# Philophrosyne.net
KiCad netlist of a schematic drawn in EAGLE
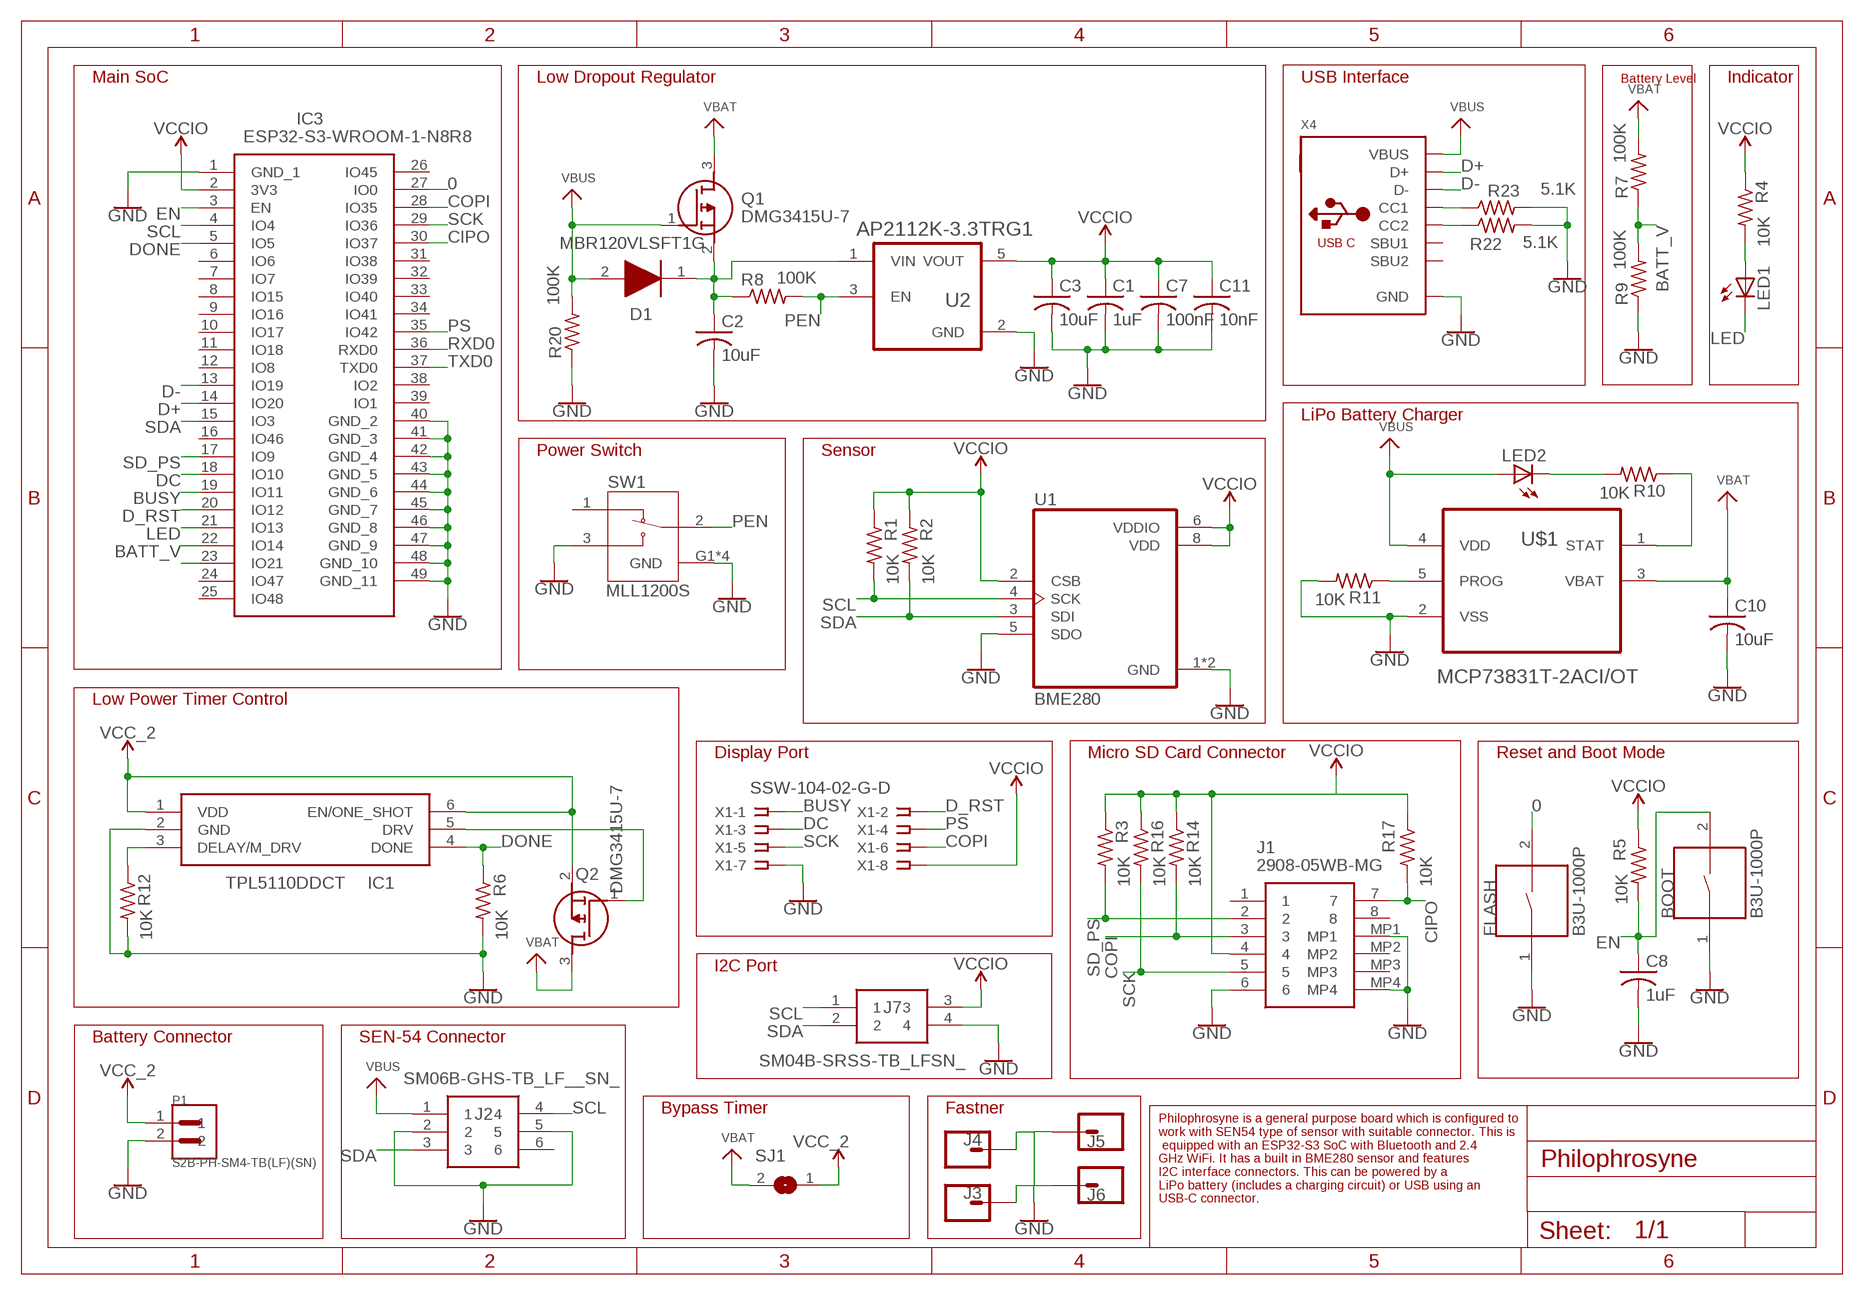
[diagram p0: schematic, sheet 1]

(export (version "E")
  (design (tool "Eeschema 10.0.6"))
  (components
    (comp (ref "BOOT")
      (value "B3U-1000P")
      (footprint "eagle-import:SW_B3U-1000P")
      (fields (field (name "MF") "Omron"))
      (libsource (lib "eagle-import") (part "B3U-1000P"))
    )
    (comp (ref "C1")
      (value "1uF")
      (footprint "eagle-import:C0402")
      (libsource (lib "eagle-import") (part "C-USC0402"))
    )
    (comp (ref "C2")
      (value "10uF")
      (footprint "eagle-import:C0402")
      (libsource (lib "eagle-import") (part "C-USC0402"))
    )
    (comp (ref "C3")
      (value "10uF")
      (footprint "eagle-import:C0402")
      (libsource (lib "eagle-import") (part "C-USC0402"))
    )
    (comp (ref "C7")
      (value "100nF")
      (footprint "eagle-import:C0402")
      (libsource (lib "eagle-import") (part "C-USC0402"))
    )
    (comp (ref "C8")
      (value "1uF")
      (footprint "eagle-import:C0402")
      (libsource (lib "eagle-import") (part "C-USC0402"))
    )
    (comp (ref "C10")
      (value "10uF")
      (footprint "eagle-import:C0402")
      (libsource (lib "eagle-import") (part "C-USC0402"))
    )
    (comp (ref "C11")
      (value "10nF")
      (footprint "eagle-import:C0402")
      (libsource (lib "eagle-import") (part "C-USC0402"))
    )
    (comp (ref "D1")
      (value "MBR120VLSFT1G")
      (footprint "eagle-import:SODFL3616X98N")
      (fields (field (name "MOUSER_PART_NUMBER") "863-MBR120VLSFT1G"))
      (libsource (lib "eagle-import") (part "MBR120VLSFT1G"))
    )
    (comp (ref "FLASH")
      (value "B3U-1000P")
      (footprint "eagle-import:SW_B3U-1000P")
      (fields (field (name "MF") "Omron"))
      (libsource (lib "eagle-import") (part "B3U-1000P"))
    )
    (comp (ref "IC1")
      (value "TPL5110DDCT")
      (footprint "eagle-import:SOT95P280X110-6N")
      (fields (field (name "MOUSER_PART_NUMBER") "595-TPL5110DDCT"))
      (libsource (lib "eagle-import") (part "TPL5110DDCT"))
    )
    (comp (ref "IC3")
      (value "ESP32-S3-WROOM-1-N8R8")
      (footprint "eagle-import:ESP32S3WROOM1N8R8")
      (fields (field (name "MOUSER_PART_NUMBER") "356-EP32S3WROOM1N8R8"))
      (libsource (lib "eagle-import") (part "ESP32-S3-WROOM-1-N8R8"))
    )
    (comp (ref "J1")
      (value "2908-05WB-MG")
      (footprint "eagle-import:290805WBMG")
      (fields (field (name "MOUSER_PART_NUMBER") "517-2908-05WB-MG"))
      (libsource (lib "eagle-import") (part "2908-05WB-MG"))
    )
    (comp (ref "J2")
      (value "SM06B-GHS-TB_LF__SN_")
      (footprint "eagle-import:SM06B-GHS-TB")
      (fields (field (name "ARROW_PART_NUMBER") "SM06B-GHS-TB(LF)(SN)"))
      (libsource (lib "eagle-import") (part "SM06B-GHS-TB_LF__SN_"))
    )
    (comp (ref "J3")
      (value "CONN_01PTH_2MM")
      (footprint "eagle-import:1X01_2MM")
      (libsource (lib "eagle-import") (part "CONN_01PTH_2MM"))
    )
    (comp (ref "J4")
      (value "CONN_01PTH_2MM")
      (footprint "eagle-import:1X01_2MM")
      (libsource (lib "eagle-import") (part "CONN_01PTH_2MM"))
    )
    (comp (ref "J5")
      (value "CONN_01PTH_2MM")
      (footprint "eagle-import:1X01_2MM")
      (libsource (lib "eagle-import") (part "CONN_01PTH_2MM"))
    )
    (comp (ref "J6")
      (value "CONN_01PTH_2MM")
      (footprint "eagle-import:1X01_2MM")
      (libsource (lib "eagle-import") (part "CONN_01PTH_2MM"))
    )
    (comp (ref "J7")
      (value "SM04B-SRSS-TB_LFSN_")
      (footprint "eagle-import:SM04B-SRSS-TB(LFSN)")
      (fields (field (name "MANUFACTURER_PART_NUMBER") "SM04B-SRSS-TB(LFSN)"))
      (libsource (lib "eagle-import") (part "SM04B-SRSS-TB_LFSN_"))
    )
    (comp (ref "LED1")
      (value "LEDCHIP-LED0603")
      (footprint "eagle-import:CHIP-LED0603")
      (libsource (lib "eagle-import") (part "LEDCHIP-LED0603"))
    )
    (comp (ref "LED2")
      (value "LEDCHIP-LED0603")
      (footprint "eagle-import:CHIP-LED0603")
      (libsource (lib "eagle-import") (part "LEDCHIP-LED0603"))
    )
    (comp (ref "P1")
      (value "S2B-PH-SM4-TB(LF)(SN)")
      (footprint "eagle-import:JST_S2B-PH-SM4-TB(LF)(SN)")
      (fields (field (name "MF") "JST Sales") (field (name "MP") "S2B-PH-SM4-TB _LF__SN_"))
      (libsource (lib "eagle-import") (part "S2B-PH-SM4-TB(LF)(SN)"))
    )
    (comp (ref "Q1")
      (value "DMG3415U-7")
      (footprint "eagle-import:SOT96P240X100-3N")
      (fields (field (name "LCSC_PART_NUMBER") "C96616"))
      (libsource (lib "eagle-import") (part "DMG3415U-7"))
    )
    (comp (ref "Q2")
      (value "DMG3415U-7")
      (footprint "eagle-import:SOT96P240X100-3N")
      (fields (field (name "LCSC_PART_NUMBER") "C96616"))
      (libsource (lib "eagle-import") (part "DMG3415U-7"))
    )
    (comp (ref "R1")
      (value "10K")
      (footprint "eagle-import:R0402")
      (libsource (lib "eagle-import") (part "R-US_R0402"))
    )
    (comp (ref "R2")
      (value "10K")
      (footprint "eagle-import:R0402")
      (libsource (lib "eagle-import") (part "R-US_R0402"))
    )
    (comp (ref "R3")
      (value "10K")
      (footprint "eagle-import:R0402")
      (libsource (lib "eagle-import") (part "R-US_R0402"))
    )
    (comp (ref "R4")
      (value "10K")
      (footprint "eagle-import:R0402")
      (libsource (lib "eagle-import") (part "R-US_R0402"))
    )
    (comp (ref "R5")
      (value "10K")
      (footprint "eagle-import:R0402")
      (libsource (lib "eagle-import") (part "R-US_R0402"))
    )
    (comp (ref "R6")
      (value "10K")
      (footprint "eagle-import:R0402")
      (libsource (lib "eagle-import") (part "R-US_R0402"))
    )
    (comp (ref "R7")
      (value "100K")
      (footprint "eagle-import:R0402")
      (libsource (lib "eagle-import") (part "R-US_R0402"))
    )
    (comp (ref "R8")
      (value "100K")
      (footprint "eagle-import:R0402")
      (libsource (lib "eagle-import") (part "R-US_R0402"))
    )
    (comp (ref "R9")
      (value "100K")
      (footprint "eagle-import:R0402")
      (libsource (lib "eagle-import") (part "R-US_R0402"))
    )
    (comp (ref "R10")
      (value "10K")
      (footprint "eagle-import:R0402")
      (libsource (lib "eagle-import") (part "R-US_R0402"))
    )
    (comp (ref "R11")
      (value "10K")
      (footprint "eagle-import:R0402")
      (libsource (lib "eagle-import") (part "R-US_R0402"))
    )
    (comp (ref "R12")
      (value "10K")
      (footprint "eagle-import:R0402")
      (libsource (lib "eagle-import") (part "R-US_R0402"))
    )
    (comp (ref "R14")
      (value "10K")
      (footprint "eagle-import:R0402")
      (libsource (lib "eagle-import") (part "R-US_R0402"))
    )
    (comp (ref "R16")
      (value "10K")
      (footprint "eagle-import:R0402")
      (libsource (lib "eagle-import") (part "R-US_R0402"))
    )
    (comp (ref "R17")
      (value "10K")
      (footprint "eagle-import:R0402")
      (libsource (lib "eagle-import") (part "R-US_R0402"))
    )
    (comp (ref "R20")
      (value "100K")
      (footprint "eagle-import:R0402")
      (libsource (lib "eagle-import") (part "R-US_R0402"))
    )
    (comp (ref "R22")
      (value "5.1K")
      (footprint "eagle-import:R0402")
      (libsource (lib "eagle-import") (part "R-US_R0402"))
    )
    (comp (ref "R23")
      (value "5.1K")
      (footprint "eagle-import:R0402")
      (libsource (lib "eagle-import") (part "R-US_R0402"))
    )
    (comp (ref "SJ1") (value "SJ") (footprint "eagle-import:SJ") (libsource (lib "eagle-import") (part "SJ")))
    (comp (ref "SW1")
      (value "MLL1200S")
      (footprint "eagle-import:SW_MLL1200S")
      (fields (field (name "COMMENT") "1437575-1") (field (name "MF") "TE Connectivity"))
      (libsource (lib "eagle-import") (part "MLL1200S"))
    )
    (comp (ref "U$1")
      (value "MCP73831T-2ACI/OT")
      (footprint "eagle-import:SOT95P280X145-5N")
      (fields (field (name "MF") "Microchip"))
      (libsource (lib "eagle-import") (part "MCP73831T-2ACI/OT"))
    )
    (comp (ref "U1")
      (value "BME280")
      (footprint "eagle-import:PSON65P250X250X100-8N")
      (fields (field (name "MF") "Bosch"))
      (libsource (lib "eagle-import") (part "BME280"))
    )
    (comp (ref "U2")
      (value "AP2112K-3.3TRG1")
      (footprint "eagle-import:SOT95P285X140-5N")
      (fields (field (name "MF") "Diodes Inc."))
      (libsource (lib "eagle-import") (part "AP2112K-3.3TRG1"))
    )
    (comp (ref "X1")
      (value "SSW-104-02-G-D")
      (footprint "eagle-import:SSW-104-02-G-D")
      (fields (field (name "MF") "Samtec Inc."))
      (libsource (lib "eagle-import") (part "SSW-104-02-G-D"))
    )
    (comp (ref "X4")
      (value "MICROBUILDER_USB_C")
      (footprint "eagle-import:MICROBUILDER_USB_C_CUSB31-CFM2AX-01-X")
      (libsource (lib "eagle-import") (part "MICROBUILDER_USB_C"))
    )
  )
  (nets
    (net (code "1") (name "/0") (class "Default")
      (node (ref "FLASH") (pin "2") (pinfunction "2_2") (pintype "passive"))
      (node (ref "IC3") (pin "27") (pinfunction "IO0_27") (pintype "bidirectional"))
    )
    (net (code "2") (name "/BATT_V") (class "Default")
      (node (ref "IC3") (pin "22") (pinfunction "IO14_22") (pintype "bidirectional"))
      (node (ref "R7") (pin "1") (pinfunction "1_1") (pintype "passive"))
      (node (ref "R9") (pin "2") (pinfunction "2_2") (pintype "passive"))
    )
    (net (code "3") (name "/BUSY") (class "Default")
      (node (ref "IC3") (pin "19") (pinfunction "IO11_19") (pintype "bidirectional"))
      (node (ref "X1") (pin "1") (pinfunction "1_1") (pintype "passive"))
    )
    (net (code "4") (name "/CIPO") (class "Default")
      (node (ref "IC3") (pin "30") (pinfunction "IO37_30") (pintype "bidirectional"))
      (node (ref "J1") (pin "7") (pinfunction "7_7") (pintype "bidirectional"))
      (node (ref "R17") (pin "2") (pinfunction "2_2") (pintype "passive"))
    )
    (net (code "5") (name "/COPI") (class "Default")
      (node (ref "IC3") (pin "28") (pinfunction "IO35_28") (pintype "bidirectional"))
      (node (ref "J1") (pin "3") (pinfunction "3_3") (pintype "bidirectional"))
      (node (ref "R14") (pin "2") (pinfunction "2_2") (pintype "passive"))
      (node (ref "X1") (pin "6") (pinfunction "1_6") (pintype "passive"))
    )
    (net (code "6") (name "/D+") (class "Default")
      (node (ref "IC3") (pin "14") (pinfunction "IO20_14") (pintype "bidirectional"))
      (node (ref "X4") (pin "A6") (pinfunction "D+_A6") (pintype "bidirectional"))
      (node (ref "X4") (pin "B6") (pinfunction "D+_B6") (pintype "bidirectional"))
    )
    (net (code "7") (name "/D-") (class "Default")
      (node (ref "IC3") (pin "13") (pinfunction "IO19_13") (pintype "bidirectional"))
      (node (ref "X4") (pin "A7") (pinfunction "D-_A7") (pintype "bidirectional"))
      (node (ref "X4") (pin "B7") (pinfunction "D-_B7") (pintype "bidirectional"))
    )
    (net (code "8") (name "/DC") (class "Default")
      (node (ref "IC3") (pin "18") (pinfunction "IO10_18") (pintype "bidirectional"))
      (node (ref "X1") (pin "3") (pinfunction "1_3") (pintype "passive"))
    )
    (net (code "9") (name "/DONE") (class "Default")
      (node (ref "IC1") (pin "4") (pinfunction "DONE_4") (pintype "bidirectional"))
      (node (ref "IC3") (pin "5") (pinfunction "IO5_5") (pintype "bidirectional"))
      (node (ref "R6") (pin "1") (pinfunction "1_1") (pintype "passive"))
    )
    (net (code "10") (name "/D_RST") (class "Default")
      (node (ref "IC3") (pin "20") (pinfunction "IO12_20") (pintype "bidirectional"))
      (node (ref "X1") (pin "2") (pinfunction "1_2") (pintype "passive"))
    )
    (net (code "11") (name "/EN") (class "Default")
      (node (ref "BOOT") (pin "2") (pinfunction "2_2") (pintype "passive"))
      (node (ref "C8") (pin "1") (pinfunction "1_1") (pintype "passive"))
      (node (ref "IC3") (pin "3") (pinfunction "EN_3") (pintype "bidirectional"))
      (node (ref "R5") (pin "2") (pinfunction "2_2") (pintype "passive"))
    )
    (net (code "12") (name "/LED") (class "Default")
      (node (ref "IC3") (pin "21") (pinfunction "IO13_21") (pintype "bidirectional"))
      (node (ref "LED1") (pin "C") (pinfunction "C_C") (pintype "passive"))
    )
    (net (code "13") (name "/PEN") (class "Default")
      (node (ref "R8") (pin "2") (pinfunction "2_2") (pintype "passive"))
      (node (ref "SW1") (pin "2") (pinfunction "2_2") (pintype "passive"))
      (node (ref "U2") (pin "3") (pinfunction "EN_3") (pintype "input"))
    )
    (net (code "14") (name "/PS") (class "Default")
      (node (ref "IC3") (pin "35") (pinfunction "IO42_35") (pintype "bidirectional"))
      (node (ref "X1") (pin "4") (pinfunction "1_4") (pintype "passive"))
    )
    (net (code "15") (name "/RXD0") (class "Default")
      (node (ref "IC3") (pin "36") (pinfunction "RXD0_36") (pintype "bidirectional"))
    )
    (net (code "16") (name "/SCK") (class "Default")
      (node (ref "IC3") (pin "29") (pinfunction "IO36_29") (pintype "bidirectional"))
      (node (ref "J1") (pin "5") (pinfunction "5_5") (pintype "bidirectional"))
      (node (ref "R16") (pin "2") (pinfunction "2_2") (pintype "passive"))
      (node (ref "X1") (pin "5") (pinfunction "1_5") (pintype "passive"))
    )
    (net (code "17") (name "/SCL") (class "Default")
      (node (ref "IC3") (pin "4") (pinfunction "IO4_4") (pintype "bidirectional"))
      (node (ref "J2") (pin "4") (pinfunction "4_4") (pintype "bidirectional"))
      (node (ref "J7") (pin "1") (pinfunction "1_1") (pintype "bidirectional"))
      (node (ref "R1") (pin "2") (pinfunction "2_2") (pintype "passive"))
      (node (ref "U1") (pin "4") (pinfunction "SCK_4") (pintype "input"))
    )
    (net (code "18") (name "/SDA") (class "Default")
      (node (ref "IC3") (pin "15") (pinfunction "IO3_15") (pintype "bidirectional"))
      (node (ref "J2") (pin "3") (pinfunction "3_3") (pintype "bidirectional"))
      (node (ref "J7") (pin "2") (pinfunction "2_2") (pintype "bidirectional"))
      (node (ref "R2") (pin "2") (pinfunction "2_2") (pintype "passive"))
      (node (ref "U1") (pin "3") (pinfunction "SDI_3") (pintype "bidirectional"))
    )
    (net (code "19") (name "/SD_PS") (class "Default")
      (node (ref "IC3") (pin "17") (pinfunction "IO9_17") (pintype "bidirectional"))
      (node (ref "J1") (pin "2") (pinfunction "2_2") (pintype "bidirectional"))
      (node (ref "R3") (pin "2") (pinfunction "2_2") (pintype "passive"))
    )
    (net (code "20") (name "/TXD0") (class "Default")
      (node (ref "IC3") (pin "37") (pinfunction "TXD0_37") (pintype "bidirectional"))
    )
    (net (code "21") (name "GND") (class "Default")
      (node (ref "BOOT") (pin "1") (pinfunction "1_1") (pintype "passive"))
      (node (ref "C1") (pin "2") (pinfunction "2_2") (pintype "passive"))
      (node (ref "C10") (pin "2") (pinfunction "2_2") (pintype "passive"))
      (node (ref "C11") (pin "2") (pinfunction "2_2") (pintype "passive"))
      (node (ref "C2") (pin "2") (pinfunction "2_2") (pintype "passive"))
      (node (ref "C3") (pin "2") (pinfunction "2_2") (pintype "passive"))
      (node (ref "C7") (pin "2") (pinfunction "2_2") (pintype "passive"))
      (node (ref "C8") (pin "2") (pinfunction "2_2") (pintype "passive"))
      (node (ref "FLASH") (pin "1") (pinfunction "1_1") (pintype "passive"))
      (node (ref "IC1") (pin "2") (pinfunction "GND_2") (pintype "bidirectional"))
      (node (ref "IC3") (pin "1") (pinfunction "GND_1_1") (pintype "bidirectional"))
      (node (ref "IC3") (pin "40") (pinfunction "GND_2_40") (pintype "bidirectional"))
      (node (ref "IC3") (pin "41") (pinfunction "GND_3_41") (pintype "bidirectional"))
      (node (ref "IC3") (pin "42") (pinfunction "GND_4_42") (pintype "bidirectional"))
      (node (ref "IC3") (pin "43") (pinfunction "GND_5_43") (pintype "bidirectional"))
      (node (ref "IC3") (pin "44") (pinfunction "GND_6_44") (pintype "bidirectional"))
      (node (ref "IC3") (pin "45") (pinfunction "GND_7_45") (pintype "bidirectional"))
      (node (ref "IC3") (pin "46") (pinfunction "GND_8_46") (pintype "bidirectional"))
      (node (ref "IC3") (pin "47") (pinfunction "GND_9_47") (pintype "bidirectional"))
      (node (ref "IC3") (pin "48") (pinfunction "GND_10_48") (pintype "bidirectional"))
      (node (ref "IC3") (pin "49") (pinfunction "GND_11_49") (pintype "bidirectional"))
      (node (ref "J1") (pin "6") (pinfunction "6_6") (pintype "bidirectional"))
      (node (ref "J1") (pin "MP1") (pinfunction "MP1_MP1") (pintype "bidirectional"))
      (node (ref "J1") (pin "MP4") (pinfunction "MP4_MP4") (pintype "bidirectional"))
      (node (ref "J2") (pin "2") (pinfunction "2_2") (pintype "bidirectional"))
      (node (ref "J2") (pin "5") (pinfunction "5_5") (pintype "bidirectional"))
      (node (ref "J3") (pin "1") (pinfunction "1_1") (pintype "passive"))
      (node (ref "J4") (pin "1") (pinfunction "1_1") (pintype "passive"))
      (node (ref "J5") (pin "1") (pinfunction "1_1") (pintype "passive"))
      (node (ref "J6") (pin "1") (pinfunction "1_1") (pintype "passive"))
      (node (ref "J7") (pin "4") (pinfunction "4_4") (pintype "bidirectional"))
      (node (ref "P1") (pin "2") (pinfunction "2_2") (pintype "passive"))
      (node (ref "R11") (pin "2") (pinfunction "2_2") (pintype "passive"))
      (node (ref "R12") (pin "2") (pinfunction "2_2") (pintype "passive"))
      (node (ref "R20") (pin "1") (pinfunction "1_1") (pintype "passive"))
      (node (ref "R22") (pin "2") (pinfunction "2_2") (pintype "passive"))
      (node (ref "R23") (pin "2") (pinfunction "2_2") (pintype "passive"))
      (node (ref "R6") (pin "2") (pinfunction "2_2") (pintype "passive"))
      (node (ref "R9") (pin "1") (pinfunction "1_1") (pintype "passive"))
      (node (ref "SW1") (pin "3") (pinfunction "3_3") (pintype "passive"))
      (node (ref "SW1") (pin "G1") (pinfunction "GND_G1") (pintype "power_in"))
      (node (ref "SW1") (pin "G2") (pinfunction "GND_G2") (pintype "power_in"))
      (node (ref "SW1") (pin "G3") (pinfunction "GND_G3") (pintype "power_in"))
      (node (ref "SW1") (pin "G4") (pinfunction "GND_G4") (pintype "power_in"))
      (node (ref "U$1") (pin "2") (pinfunction "VSS_2") (pintype "power_in"))
      (node (ref "U1") (pin "1") (pinfunction "GND_1") (pintype "power_in"))
      (node (ref "U1") (pin "5") (pinfunction "SDO_5") (pintype "bidirectional"))
      (node (ref "U1") (pin "7") (pinfunction "GND_7") (pintype "power_in"))
      (node (ref "U2") (pin "2") (pinfunction "GND_2") (pintype "power_in"))
      (node (ref "X1") (pin "7") (pinfunction "1_7") (pintype "passive"))
      (node (ref "X4") (pin "A1B12") (pinfunction "GND_A1B12") (pintype "power_in"))
      (node (ref "X4") (pin "B1A12") (pinfunction "GND_B1A12") (pintype "power_in"))
    )
    (net (code "22") (name "Net-(D1-K)") (class "Default")
      (node (ref "C2") (pin "1") (pinfunction "1_1") (pintype "passive"))
      (node (ref "D1") (pin "1") (pinfunction "K_1") (pintype "bidirectional"))
      (node (ref "Q1") (pin "2") (pinfunction "S_2") (pintype "bidirectional"))
      (node (ref "R8") (pin "1") (pinfunction "1_1") (pintype "passive"))
      (node (ref "U2") (pin "1") (pinfunction "VIN_1") (pintype "power_in"))
    )
    (net (code "23") (name "Net-(IC1-DELAY{slash}M_DRV)") (class "Default")
      (node (ref "IC1") (pin "3") (pinfunction "DELAY/M_DRV_3") (pintype "bidirectional"))
      (node (ref "R12") (pin "1") (pinfunction "1_1") (pintype "passive"))
    )
    (net (code "24") (name "Net-(IC1-DRV)") (class "Default")
      (node (ref "IC1") (pin "5") (pinfunction "DRV_5") (pintype "bidirectional"))
      (node (ref "Q2") (pin "1") (pinfunction "G_1") (pintype "bidirectional"))
    )
    (net (code "25") (name "Net-(LED1-PadA)") (class "Default")
      (node (ref "LED1") (pin "A") (pinfunction "A_A") (pintype "passive"))
      (node (ref "R4") (pin "2") (pinfunction "2_2") (pintype "passive"))
    )
    (net (code "26") (name "Net-(LED2-PadC)") (class "Default")
      (node (ref "LED2") (pin "C") (pinfunction "C_C") (pintype "passive"))
      (node (ref "R10") (pin "2") (pinfunction "2_2") (pintype "passive"))
    )
    (net (code "27") (name "Net-(U$1-PROG)") (class "Default")
      (node (ref "R11") (pin "1") (pinfunction "1_1") (pintype "passive"))
      (node (ref "U$1") (pin "5") (pinfunction "PROG_5") (pintype "input"))
    )
    (net (code "28") (name "Net-(U$1-STAT)") (class "Default")
      (node (ref "R10") (pin "1") (pinfunction "1_1") (pintype "passive"))
      (node (ref "U$1") (pin "1") (pinfunction "STAT_1") (pintype "output"))
    )
    (net (code "29") (name "Net-(X4-CC1)") (class "Default")
      (node (ref "R23") (pin "1") (pinfunction "1_1") (pintype "passive"))
      (node (ref "X4") (pin "A5") (pinfunction "CC1_A5") (pintype "bidirectional"))
    )
    (net (code "30") (name "Net-(X4-CC2)") (class "Default")
      (node (ref "R22") (pin "1") (pinfunction "1_1") (pintype "passive"))
      (node (ref "X4") (pin "B5") (pinfunction "CC2_B5") (pintype "bidirectional"))
    )
    (net (code "31") (name "VBAT") (class "Default")
      (node (ref "C10") (pin "1") (pinfunction "1_1") (pintype "passive"))
      (node (ref "Q1") (pin "3") (pinfunction "D_3") (pintype "bidirectional"))
      (node (ref "Q2") (pin "3") (pinfunction "D_3") (pintype "bidirectional"))
      (node (ref "R7") (pin "2") (pinfunction "2_2") (pintype "passive"))
      (node (ref "SJ1") (pin "2") (pinfunction "2_2") (pintype "passive"))
      (node (ref "U$1") (pin "3") (pinfunction "VBAT_3") (pintype "output"))
    )
    (net (code "32") (name "VBUS") (class "Default")
      (node (ref "D1") (pin "2") (pinfunction "A_2") (pintype "bidirectional"))
      (node (ref "J2") (pin "1") (pinfunction "1_1") (pintype "bidirectional"))
      (node (ref "LED2") (pin "A") (pinfunction "A_A") (pintype "passive"))
      (node (ref "Q1") (pin "1") (pinfunction "G_1") (pintype "bidirectional"))
      (node (ref "R20") (pin "2") (pinfunction "2_2") (pintype "passive"))
      (node (ref "U$1") (pin "4") (pinfunction "VDD_4") (pintype "power_in"))
      (node (ref "X4") (pin "A4B9") (pinfunction "VBUS_A4B9") (pintype "power_in"))
      (node (ref "X4") (pin "B4A9") (pinfunction "VBUS_B4A9") (pintype "power_in"))
    )
    (net (code "33") (name "VCCIO") (class "Default")
      (node (ref "C1") (pin "1") (pinfunction "1_1") (pintype "passive"))
      (node (ref "C11") (pin "1") (pinfunction "1_1") (pintype "passive"))
      (node (ref "C3") (pin "1") (pinfunction "1_1") (pintype "passive"))
      (node (ref "C7") (pin "1") (pinfunction "1_1") (pintype "passive"))
      (node (ref "IC3") (pin "2") (pinfunction "3V3_2") (pintype "bidirectional"))
      (node (ref "J1") (pin "4") (pinfunction "4_4") (pintype "bidirectional"))
      (node (ref "J7") (pin "3") (pinfunction "3_3") (pintype "bidirectional"))
      (node (ref "R1") (pin "1") (pinfunction "1_1") (pintype "passive"))
      (node (ref "R14") (pin "1") (pinfunction "1_1") (pintype "passive"))
      (node (ref "R16") (pin "1") (pinfunction "1_1") (pintype "passive"))
      (node (ref "R17") (pin "1") (pinfunction "1_1") (pintype "passive"))
      (node (ref "R2") (pin "1") (pinfunction "1_1") (pintype "passive"))
      (node (ref "R3") (pin "1") (pinfunction "1_1") (pintype "passive"))
      (node (ref "R4") (pin "1") (pinfunction "1_1") (pintype "passive"))
      (node (ref "R5") (pin "1") (pinfunction "1_1") (pintype "passive"))
      (node (ref "U1") (pin "2") (pinfunction "CSB_2") (pintype "input"))
      (node (ref "U1") (pin "6") (pinfunction "VDDIO_6") (pintype "power_in"))
      (node (ref "U1") (pin "8") (pinfunction "VDD_8") (pintype "power_in"))
      (node (ref "U2") (pin "5") (pinfunction "VOUT_5") (pintype "power_in"))
      (node (ref "X1") (pin "8") (pinfunction "1_8") (pintype "passive"))
    )
    (net (code "34") (name "VCC_2") (class "Default")
      (node (ref "IC1") (pin "1") (pinfunction "VDD_1") (pintype "bidirectional"))
      (node (ref "IC1") (pin "6") (pinfunction "EN/ONE_SHOT_6") (pintype "bidirectional"))
      (node (ref "P1") (pin "1") (pinfunction "1_1") (pintype "passive"))
      (node (ref "Q2") (pin "2") (pinfunction "S_2") (pintype "bidirectional"))
      (node (ref "SJ1") (pin "1") (pinfunction "1_1") (pintype "passive"))
    )
    (net (code "35") (name "unconnected-(IC3-IO1-Pad39)") (class "Default")
      (node (ref "IC3") (pin "39") (pinfunction "IO1_39") (pintype "bidirectional"))
    )
    (net (code "36") (name "unconnected-(IC3-IO2-Pad38)") (class "Default")
      (node (ref "IC3") (pin "38") (pinfunction "IO2_38") (pintype "bidirectional"))
    )
    (net (code "37") (name "unconnected-(IC3-IO6-Pad6)") (class "Default")
      (node (ref "IC3") (pin "6") (pinfunction "IO6_6") (pintype "bidirectional"))
    )
    (net (code "38") (name "unconnected-(IC3-IO7-Pad7)") (class "Default")
      (node (ref "IC3") (pin "7") (pinfunction "IO7_7") (pintype "bidirectional"))
    )
    (net (code "39") (name "unconnected-(IC3-IO8-Pad12)") (class "Default")
      (node (ref "IC3") (pin "12") (pinfunction "IO8_12") (pintype "bidirectional"))
    )
    (net (code "40") (name "unconnected-(IC3-IO15-Pad8)") (class "Default")
      (node (ref "IC3") (pin "8") (pinfunction "IO15_8") (pintype "bidirectional"))
    )
    (net (code "41") (name "unconnected-(IC3-IO16-Pad9)") (class "Default")
      (node (ref "IC3") (pin "9") (pinfunction "IO16_9") (pintype "bidirectional"))
    )
    (net (code "42") (name "unconnected-(IC3-IO17-Pad10)") (class "Default")
      (node (ref "IC3") (pin "10") (pinfunction "IO17_10") (pintype "bidirectional"))
    )
    (net (code "43") (name "unconnected-(IC3-IO18-Pad11)") (class "Default")
      (node (ref "IC3") (pin "11") (pinfunction "IO18_11") (pintype "bidirectional"))
    )
    (net (code "44") (name "unconnected-(IC3-IO21-Pad23)") (class "Default")
      (node (ref "IC3") (pin "23") (pinfunction "IO21_23") (pintype "bidirectional"))
    )
    (net (code "45") (name "unconnected-(IC3-IO38-Pad31)") (class "Default")
      (node (ref "IC3") (pin "31") (pinfunction "IO38_31") (pintype "bidirectional"))
    )
    (net (code "46") (name "unconnected-(IC3-IO39-Pad32)") (class "Default")
      (node (ref "IC3") (pin "32") (pinfunction "IO39_32") (pintype "bidirectional"))
    )
    (net (code "47") (name "unconnected-(IC3-IO40-Pad33)") (class "Default")
      (node (ref "IC3") (pin "33") (pinfunction "IO40_33") (pintype "bidirectional"))
    )
    (net (code "48") (name "unconnected-(IC3-IO41-Pad34)") (class "Default")
      (node (ref "IC3") (pin "34") (pinfunction "IO41_34") (pintype "bidirectional"))
    )
    (net (code "49") (name "unconnected-(IC3-IO45-Pad26)") (class "Default")
      (node (ref "IC3") (pin "26") (pinfunction "IO45_26") (pintype "bidirectional"))
    )
    (net (code "50") (name "unconnected-(IC3-IO46-Pad16)") (class "Default")
      (node (ref "IC3") (pin "16") (pinfunction "IO46_16") (pintype "bidirectional"))
    )
    (net (code "51") (name "unconnected-(IC3-IO47-Pad24)") (class "Default")
      (node (ref "IC3") (pin "24") (pinfunction "IO47_24") (pintype "bidirectional"))
    )
    (net (code "52") (name "unconnected-(IC3-IO48-Pad25)") (class "Default")
      (node (ref "IC3") (pin "25") (pinfunction "IO48_25") (pintype "bidirectional"))
    )
    (net (code "53") (name "unconnected-(J1-Pad1)") (class "Default")
      (node (ref "J1") (pin "1") (pinfunction "1_1") (pintype "bidirectional"))
    )
    (net (code "54") (name "unconnected-(J1-Pad8)") (class "Default")
      (node (ref "J1") (pin "8") (pinfunction "8_8") (pintype "bidirectional"))
    )
    (net (code "55") (name "unconnected-(J1-PadMP2)") (class "Default")
      (node (ref "J1") (pin "MP2") (pinfunction "MP2_MP2") (pintype "bidirectional"))
    )
    (net (code "56") (name "unconnected-(J1-PadMP3)") (class "Default")
      (node (ref "J1") (pin "MP3") (pinfunction "MP3_MP3") (pintype "bidirectional"))
    )
    (net (code "57") (name "unconnected-(J2-Pad6)") (class "Default")
      (node (ref "J2") (pin "6") (pinfunction "6_6") (pintype "bidirectional"))
    )
    (net (code "58") (name "unconnected-(SW1-Pad1)") (class "Default")
      (node (ref "SW1") (pin "1") (pinfunction "1_1") (pintype "passive"))
    )
    (net (code "59") (name "unconnected-(X4-SBU1-PadA8)") (class "Default")
      (node (ref "X4") (pin "A8") (pinfunction "SBU1_A8") (pintype "bidirectional"))
    )
    (net (code "60") (name "unconnected-(X4-SBU2-PadB8)") (class "Default")
      (node (ref "X4") (pin "B8") (pinfunction "SBU2_B8") (pintype "bidirectional"))
    )
  )
)
